# bristol_longshot.net
KiCad netlist of a schematic drawn in EAGLE
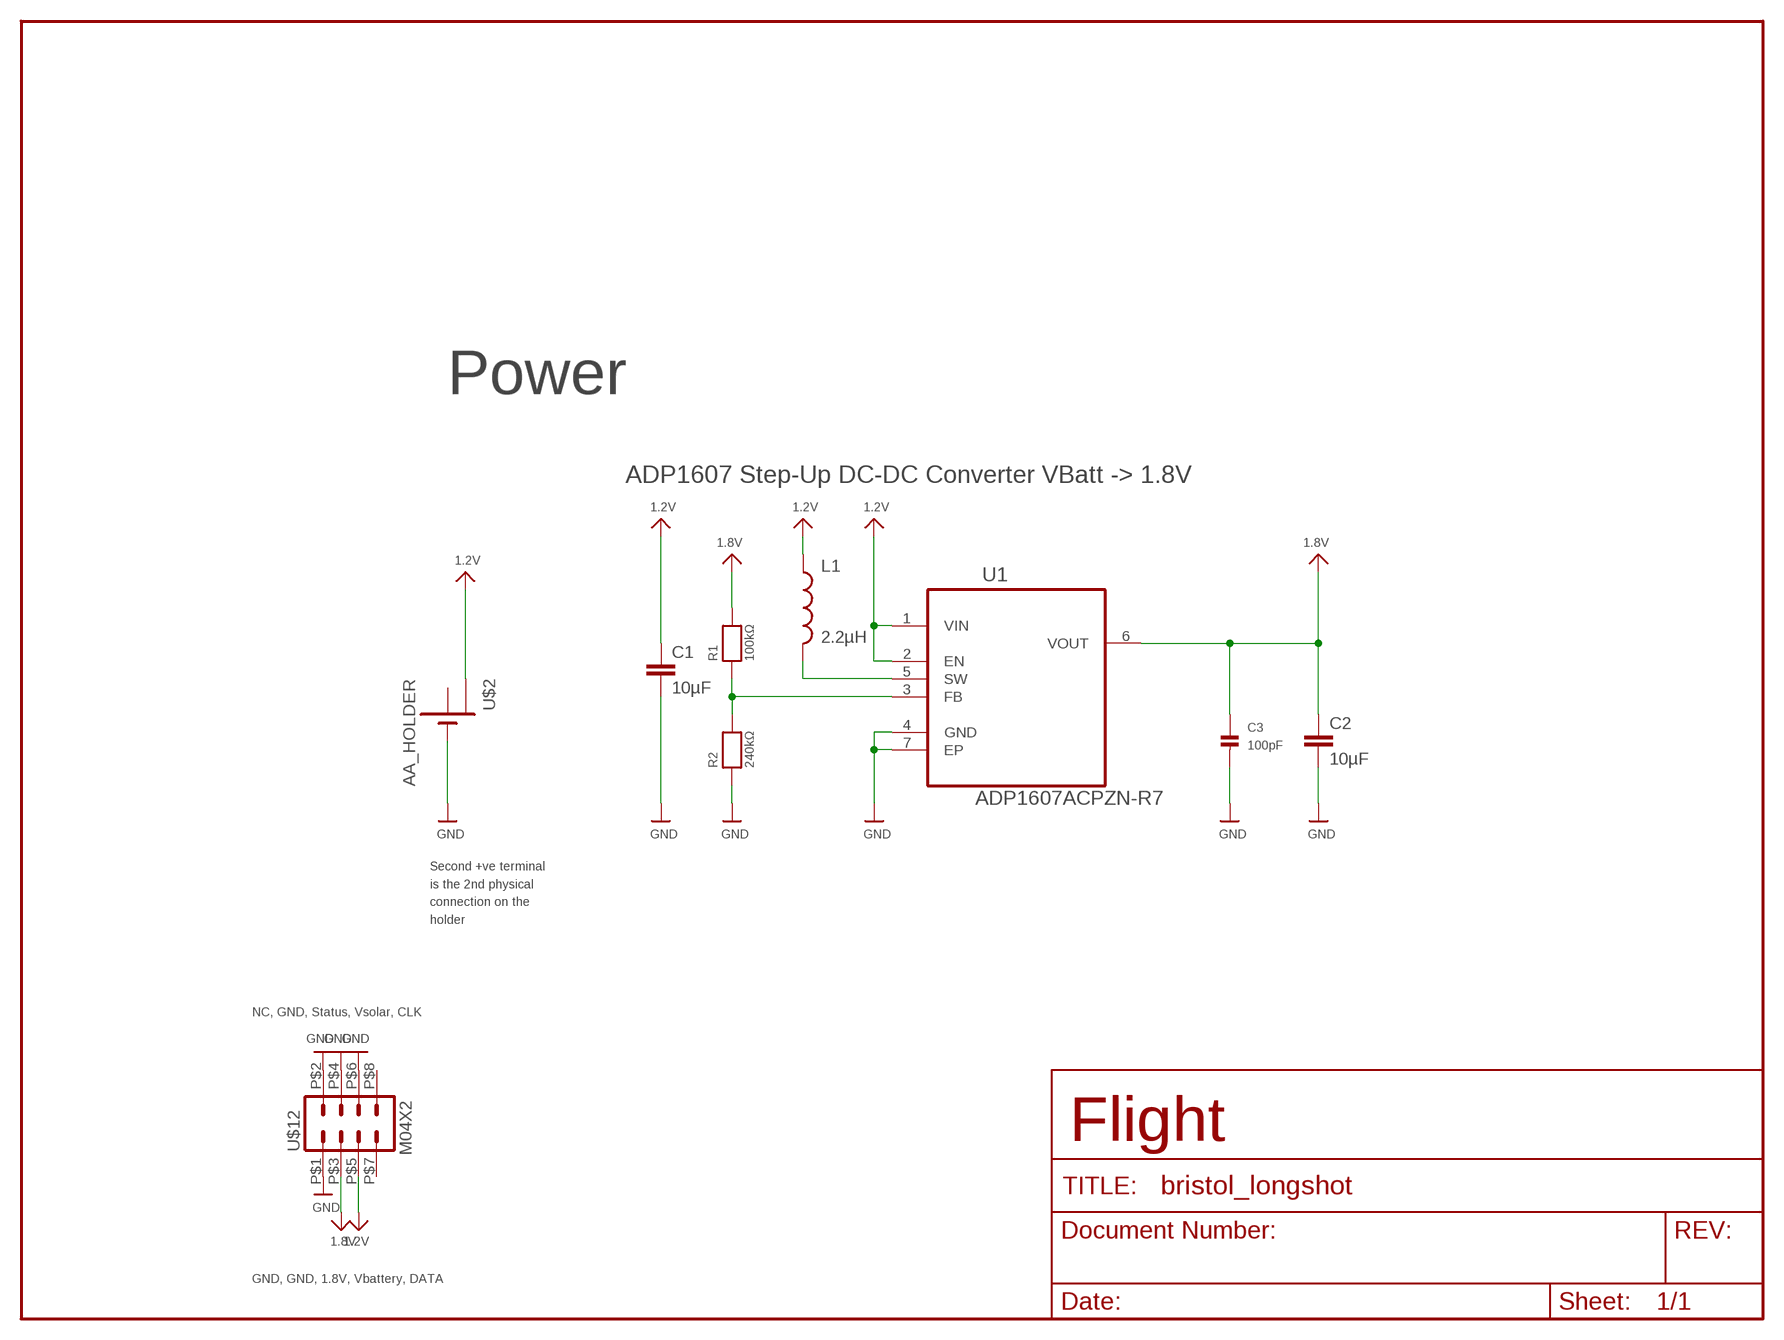
[diagram p0: schematic, sheet 1]

(export (version "E")
  (design (tool "Eeschema 10.0.6"))
  (components
    (comp (ref "C1")
      (value "10µF")
      (footprint "eagle-import:C0603K")
      (libsource (lib "eagle-import") (part "C-EUC0603K"))
    )
    (comp (ref "C2")
      (value "10µF")
      (footprint "eagle-import:C0603K")
      (libsource (lib "eagle-import") (part "C-EUC0603K"))
    )
    (comp (ref "C3")
      (value "100pF")
      (footprint "eagle-import:_0402")
      (libsource (lib "eagle-import") (part "CAP_CERAMIC_0402"))
    )
    (comp (ref "L1")
      (value "2.2µH")
      (footprint "eagle-import:1007")
      (libsource (lib "eagle-import") (part "INDUCTOR1007"))
    )
    (comp (ref "R1")
      (value "100kΩ")
      (footprint "eagle-import:_0402")
      (libsource (lib "eagle-import") (part "RESISTOR_0402"))
    )
    (comp (ref "R2")
      (value "240kΩ")
      (footprint "eagle-import:_0402")
      (libsource (lib "eagle-import") (part "RESISTOR_0402"))
    )
    (comp (ref "U$2")
      (value "AA_HOLDER")
      (footprint "eagle-import:AA")
      (libsource (lib "eagle-import") (part "AA_HOLDER"))
    )
    (comp (ref "U$12")
      (value "M04X2")
      (footprint "eagle-import:M04X2")
      (libsource (lib "eagle-import") (part "M04X2"))
    )
    (comp (ref "U1")
      (value "ADP1607ACPZN-R7")
      (footprint "eagle-import:DFN200X200X60-7N")
      (libsource (lib "eagle-import") (part "ADP1607ACPZN-R7"))
    )
  )
  (nets
    (net (code "1") (name "/+") (class "Default")
      (node (ref "U$2") (pin "+2") (pinfunction "+_+2") (pintype "power_in"))
    )
    (net (code "2") (name "1.2V") (class "Default")
      (node (ref "C1") (pin "1") (pinfunction "1_1") (pintype "passive"))
      (node (ref "L1") (pin "1") (pinfunction "1_1") (pintype "passive"))
      (node (ref "U$12") (pin "P$5") (pinfunction "5_P$5") (pintype "passive"))
      (node (ref "U$2") (pin "+1") (pinfunction "+2_+1") (pintype "power_in"))
      (node (ref "U1") (pin "1") (pinfunction "VIN_1") (pintype "power_in"))
      (node (ref "U1") (pin "2") (pinfunction "EN_2") (pintype "input"))
    )
    (net (code "3") (name "1.8V") (class "Default")
      (node (ref "C2") (pin "1") (pinfunction "1_1") (pintype "passive"))
      (node (ref "C3") (pin "1") (pinfunction "P$1_1") (pintype "passive"))
      (node (ref "R1") (pin "2") (pinfunction "2_2") (pintype "passive"))
      (node (ref "U$12") (pin "P$3") (pinfunction "3_P$3") (pintype "passive"))
      (node (ref "U1") (pin "6") (pinfunction "VOUT_6") (pintype "output"))
    )
    (net (code "4") (name "GND") (class "Default")
      (node (ref "C1") (pin "2") (pinfunction "2_2") (pintype "passive"))
      (node (ref "C2") (pin "2") (pinfunction "2_2") (pintype "passive"))
      (node (ref "C3") (pin "2") (pinfunction "P$2_2") (pintype "passive"))
      (node (ref "R2") (pin "1") (pinfunction "1_1") (pintype "passive"))
      (node (ref "U$12") (pin "P$1") (pinfunction "1_P$1") (pintype "passive"))
      (node (ref "U$12") (pin "P$2") (pinfunction "2_P$2") (pintype "passive"))
      (node (ref "U$12") (pin "P$4") (pinfunction "4_P$4") (pintype "passive"))
      (node (ref "U$12") (pin "P$6") (pinfunction "6_P$6") (pintype "passive"))
      (node (ref "U$2") (pin "-1") (pinfunction "-_-1") (pintype "power_in"))
      (node (ref "U$2") (pin "-2") (pinfunction "-_-2") (pintype "power_in"))
      (node (ref "U1") (pin "4") (pinfunction "GND_4") (pintype "power_in"))
      (node (ref "U1") (pin "7") (pinfunction "EP_7") (pintype "passive"))
    )
    (net (code "5") (name "Net-(U1-FB)") (class "Default")
      (node (ref "R1") (pin "1") (pinfunction "1_1") (pintype "passive"))
      (node (ref "R2") (pin "2") (pinfunction "2_2") (pintype "passive"))
      (node (ref "U1") (pin "3") (pinfunction "FB_3") (pintype "passive"))
    )
    (net (code "6") (name "Net-(U1-SW)") (class "Default")
      (node (ref "L1") (pin "2") (pinfunction "2_2") (pintype "passive"))
      (node (ref "U1") (pin "5") (pinfunction "SW_5") (pintype "passive"))
    )
    (net (code "7") (name "unconnected-(U$12-7-PadP$7)") (class "Default")
      (node (ref "U$12") (pin "P$7") (pinfunction "7_P$7") (pintype "passive"))
    )
    (net (code "8") (name "unconnected-(U$12-8-PadP$8)") (class "Default")
      (node (ref "U$12") (pin "P$8") (pinfunction "8_P$8") (pintype "passive"))
    )
  )
)
